# 08_MISC.net
KiCad netlist of a schematic drawn in Altium Designer
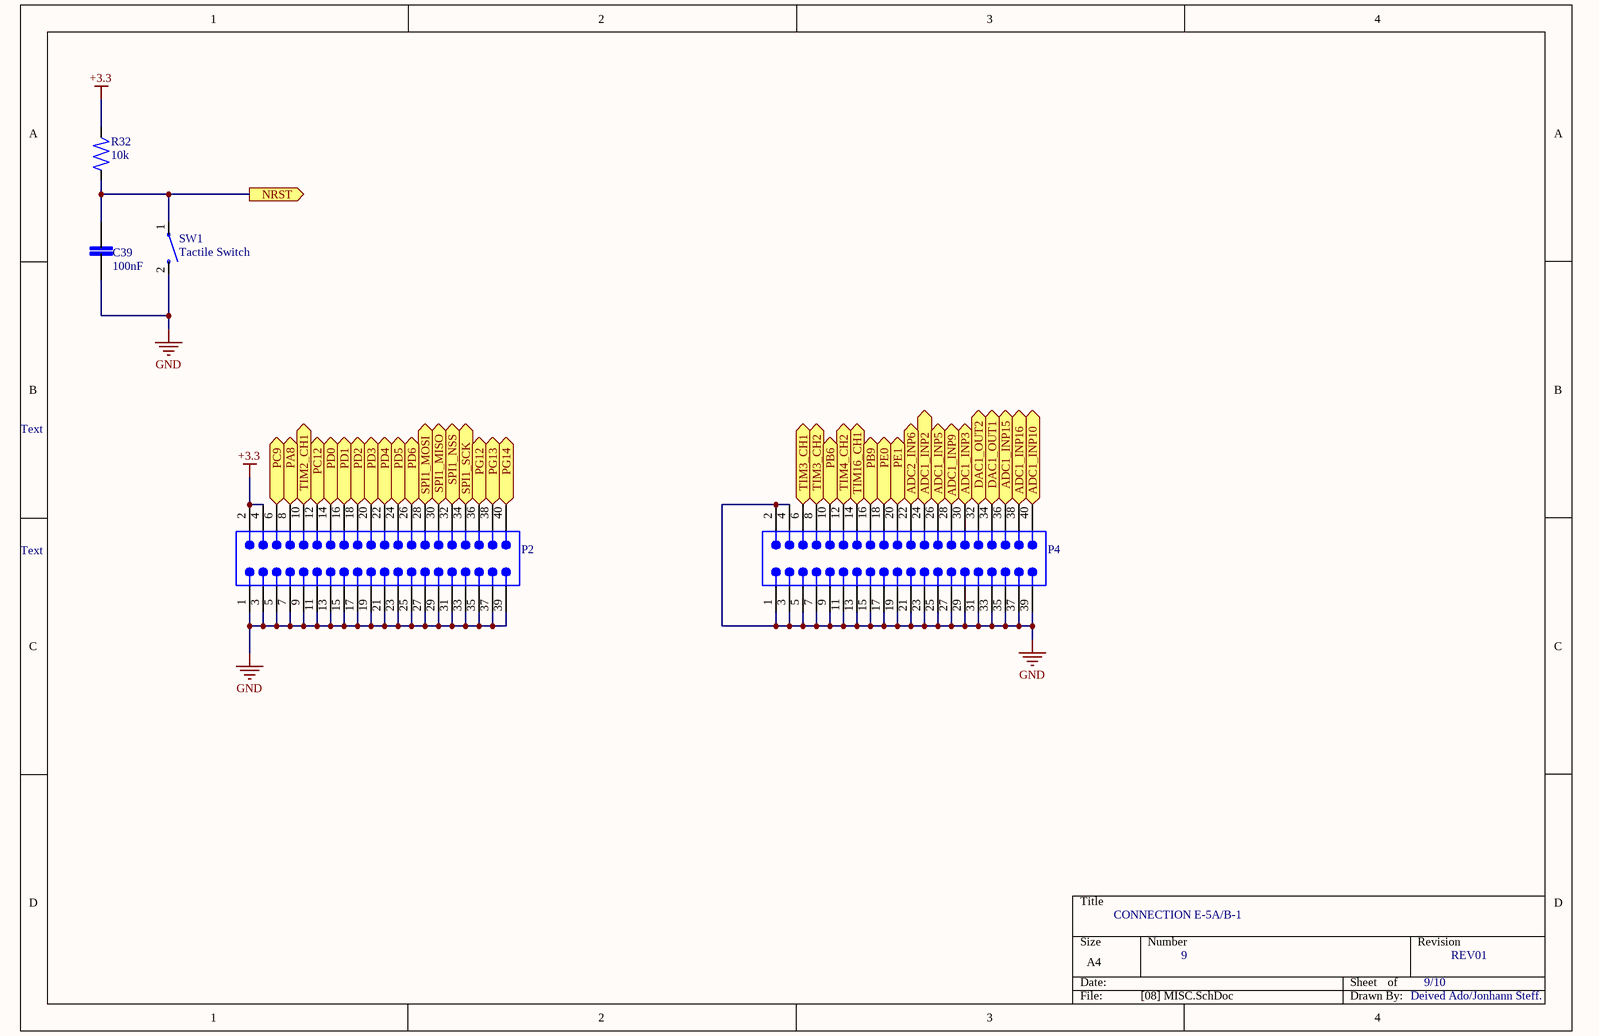
[diagram p0: [08] MISC.SchDoc]

(export (version "E")
  (design (tool "Eeschema 10.0.6"))
  (components
    (comp (ref "C39")
      (value "100nF")
      (footprint "CAP_0603")
      (description "Generic capacitor symbol")
      (libsource (lib "Integrated_Library_IST") (part "C_Small"))
    )
    (comp (ref "P2")
      (value "62504021621")
      (footprint "62504021621")
      (description "WR-BHD Male Box Header, THT Straight, pitch 2mm, 2 row, 40 pin")
      (fields (field (name "MANUFACTURER") "Wurth Elektronik"))
      (libsource (lib "WE - Electromechanical Components") (part "Header_Male_2R_40P"))
    )
    (comp (ref "P4")
      (value "62504021621")
      (footprint "62504021621")
      (description "WR-BHD Male Box Header, THT Straight, pitch 2mm, 2 row, 40 pin")
      (fields (field (name "MANUFACTURER") "Wurth Elektronik"))
      (libsource (lib "WE - Electromechanical Components") (part "Header_Male_2R_40P"))
    )
    (comp (ref "R32")
      (value "10k")
      (footprint "RES_0603")
      (description "Generic Resistor symbol")
      (libsource (lib "Integrated_Library_IST") (part "R_Small"))
    )
    (comp (ref "SW1")
      (value "Tactile Switch")
      (footprint "SW_1437566-3")
      (description "Switch Tactile OFF (ON) SPST Rectangular Button Gull Wing 0.05A 12VDC SMD Loose Piece")
      (fields
        (field (name "MANUFACTURER") "TE Connectivity / Alcoswitch")
        (field (name "MFR. PART #") "FSMSM")
      )
      (libsource (lib "Integrated_Library_IST") (part "Tactile Switch"))
    )
  )
  (nets
    (net (code "1") (name "+3.3") (class "Default")
      (node (ref "P2") (pin "2") (pinfunction "2_2") (pintype "passive"))
      (node (ref "P2") (pin "4") (pinfunction "4_4") (pintype "passive"))
      (node (ref "R32") (pin "2") (pinfunction "2_2") (pintype "passive"))
    )
    (net (code "2") (name "/ADC1_INP2") (class "Default")
      (node (ref "P4") (pin "24") (pinfunction "24_24") (pintype "passive"))
    )
    (net (code "3") (name "/ADC1_INP3") (class "Default")
      (node (ref "P4") (pin "30") (pinfunction "30_30") (pintype "passive"))
    )
    (net (code "4") (name "/ADC1_INP5") (class "Default")
      (node (ref "P4") (pin "26") (pinfunction "26_26") (pintype "passive"))
    )
    (net (code "5") (name "/ADC1_INP9") (class "Default")
      (node (ref "P4") (pin "28") (pinfunction "28_28") (pintype "passive"))
    )
    (net (code "6") (name "/ADC1_INP10") (class "Default")
      (node (ref "P4") (pin "40") (pinfunction "40_40") (pintype "passive"))
    )
    (net (code "7") (name "/ADC1_INP15") (class "Default")
      (node (ref "P4") (pin "36") (pinfunction "36_36") (pintype "passive"))
    )
    (net (code "8") (name "/ADC1_INP16") (class "Default")
      (node (ref "P4") (pin "38") (pinfunction "38_38") (pintype "passive"))
    )
    (net (code "9") (name "/ADC2_INP6") (class "Default")
      (node (ref "P4") (pin "22") (pinfunction "22_22") (pintype "passive"))
    )
    (net (code "10") (name "/DAC1_OUT1") (class "Default")
      (node (ref "P4") (pin "34") (pinfunction "34_34") (pintype "passive"))
    )
    (net (code "11") (name "/DAC1_OUT2") (class "Default")
      (node (ref "P4") (pin "32") (pinfunction "32_32") (pintype "passive"))
    )
    (net (code "12") (name "/NRST") (class "Default")
      (node (ref "C39") (pin "2") (pinfunction "2_2") (pintype "passive"))
      (node (ref "R32") (pin "1") (pinfunction "1_1") (pintype "passive"))
      (node (ref "SW1") (pin "1") (pinfunction "1_1") (pintype "passive"))
    )
    (net (code "13") (name "/PA8") (class "Default")
      (node (ref "P2") (pin "8") (pinfunction "8_8") (pintype "passive"))
    )
    (net (code "14") (name "/PB6") (class "Default")
      (node (ref "P4") (pin "10") (pinfunction "10_10") (pintype "passive"))
    )
    (net (code "15") (name "/PB9") (class "Default")
      (node (ref "P4") (pin "16") (pinfunction "16_16") (pintype "passive"))
    )
    (net (code "16") (name "/PC9") (class "Default")
      (node (ref "P2") (pin "6") (pinfunction "6_6") (pintype "passive"))
    )
    (net (code "17") (name "/PC12") (class "Default")
      (node (ref "P2") (pin "12") (pinfunction "12_12") (pintype "passive"))
    )
    (net (code "18") (name "/PD0") (class "Default")
      (node (ref "P2") (pin "14") (pinfunction "14_14") (pintype "passive"))
    )
    (net (code "19") (name "/PD1") (class "Default")
      (node (ref "P2") (pin "16") (pinfunction "16_16") (pintype "passive"))
    )
    (net (code "20") (name "/PD2") (class "Default")
      (node (ref "P2") (pin "18") (pinfunction "18_18") (pintype "passive"))
    )
    (net (code "21") (name "/PD3") (class "Default")
      (node (ref "P2") (pin "20") (pinfunction "20_20") (pintype "passive"))
    )
    (net (code "22") (name "/PD4") (class "Default")
      (node (ref "P2") (pin "22") (pinfunction "22_22") (pintype "passive"))
    )
    (net (code "23") (name "/PD5") (class "Default")
      (node (ref "P2") (pin "24") (pinfunction "24_24") (pintype "passive"))
    )
    (net (code "24") (name "/PD6") (class "Default")
      (node (ref "P2") (pin "26") (pinfunction "26_26") (pintype "passive"))
    )
    (net (code "25") (name "/PE0") (class "Default")
      (node (ref "P4") (pin "18") (pinfunction "18_18") (pintype "passive"))
    )
    (net (code "26") (name "/PE1") (class "Default")
      (node (ref "P4") (pin "20") (pinfunction "20_20") (pintype "passive"))
    )
    (net (code "27") (name "/PG12") (class "Default")
      (node (ref "P2") (pin "36") (pinfunction "36_36") (pintype "passive"))
    )
    (net (code "28") (name "/PG13") (class "Default")
      (node (ref "P2") (pin "38") (pinfunction "38_38") (pintype "passive"))
    )
    (net (code "29") (name "/PG14") (class "Default")
      (node (ref "P2") (pin "40") (pinfunction "40_40") (pintype "passive"))
    )
    (net (code "30") (name "/SPI1_MISO") (class "Default")
      (node (ref "P2") (pin "30") (pinfunction "30_30") (pintype "passive"))
    )
    (net (code "31") (name "/SPI1_MOSI") (class "Default")
      (node (ref "P2") (pin "28") (pinfunction "28_28") (pintype "passive"))
    )
    (net (code "32") (name "/SPI1_NSS") (class "Default")
      (node (ref "P2") (pin "32") (pinfunction "32_32") (pintype "passive"))
    )
    (net (code "33") (name "/SPI1_SCK") (class "Default")
      (node (ref "P2") (pin "34") (pinfunction "34_34") (pintype "passive"))
    )
    (net (code "34") (name "/TIM2_CH1") (class "Default")
      (node (ref "P2") (pin "10") (pinfunction "10_10") (pintype "passive"))
    )
    (net (code "35") (name "/TIM3_CH1") (class "Default")
      (node (ref "P4") (pin "6") (pinfunction "6_6") (pintype "passive"))
    )
    (net (code "36") (name "/TIM3_CH2") (class "Default")
      (node (ref "P4") (pin "8") (pinfunction "8_8") (pintype "passive"))
    )
    (net (code "37") (name "/TIM4_CH2") (class "Default")
      (node (ref "P4") (pin "12") (pinfunction "12_12") (pintype "passive"))
    )
    (net (code "38") (name "/TIM16_CH1") (class "Default")
      (node (ref "P4") (pin "14") (pinfunction "14_14") (pintype "passive"))
    )
    (net (code "39") (name "GND") (class "Default")
      (node (ref "C39") (pin "1") (pinfunction "1_1") (pintype "passive"))
      (node (ref "P2") (pin "1") (pinfunction "1_1") (pintype "passive"))
      (node (ref "P2") (pin "11") (pinfunction "11_11") (pintype "passive"))
      (node (ref "P2") (pin "13") (pinfunction "13_13") (pintype "passive"))
      (node (ref "P2") (pin "15") (pinfunction "15_15") (pintype "passive"))
      (node (ref "P2") (pin "17") (pinfunction "17_17") (pintype "passive"))
      (node (ref "P2") (pin "19") (pinfunction "19_19") (pintype "passive"))
      (node (ref "P2") (pin "21") (pinfunction "21_21") (pintype "passive"))
      (node (ref "P2") (pin "23") (pinfunction "23_23") (pintype "passive"))
      (node (ref "P2") (pin "25") (pinfunction "25_25") (pintype "passive"))
      (node (ref "P2") (pin "27") (pinfunction "27_27") (pintype "passive"))
      (node (ref "P2") (pin "29") (pinfunction "29_29") (pintype "passive"))
      (node (ref "P2") (pin "3") (pinfunction "3_3") (pintype "passive"))
      (node (ref "P2") (pin "31") (pinfunction "31_31") (pintype "passive"))
      (node (ref "P2") (pin "33") (pinfunction "33_33") (pintype "passive"))
      (node (ref "P2") (pin "35") (pinfunction "35_35") (pintype "passive"))
      (node (ref "P2") (pin "37") (pinfunction "37_37") (pintype "passive"))
      (node (ref "P2") (pin "39") (pinfunction "39_39") (pintype "passive"))
      (node (ref "P2") (pin "5") (pinfunction "5_5") (pintype "passive"))
      (node (ref "P2") (pin "7") (pinfunction "7_7") (pintype "passive"))
      (node (ref "P2") (pin "9") (pinfunction "9_9") (pintype "passive"))
      (node (ref "P4") (pin "1") (pinfunction "1_1") (pintype "passive"))
      (node (ref "P4") (pin "11") (pinfunction "11_11") (pintype "passive"))
      (node (ref "P4") (pin "13") (pinfunction "13_13") (pintype "passive"))
      (node (ref "P4") (pin "15") (pinfunction "15_15") (pintype "passive"))
      (node (ref "P4") (pin "17") (pinfunction "17_17") (pintype "passive"))
      (node (ref "P4") (pin "19") (pinfunction "19_19") (pintype "passive"))
      (node (ref "P4") (pin "2") (pinfunction "2_2") (pintype "passive"))
      (node (ref "P4") (pin "21") (pinfunction "21_21") (pintype "passive"))
      (node (ref "P4") (pin "23") (pinfunction "23_23") (pintype "passive"))
      (node (ref "P4") (pin "25") (pinfunction "25_25") (pintype "passive"))
      (node (ref "P4") (pin "27") (pinfunction "27_27") (pintype "passive"))
      (node (ref "P4") (pin "29") (pinfunction "29_29") (pintype "passive"))
      (node (ref "P4") (pin "3") (pinfunction "3_3") (pintype "passive"))
      (node (ref "P4") (pin "31") (pinfunction "31_31") (pintype "passive"))
      (node (ref "P4") (pin "33") (pinfunction "33_33") (pintype "passive"))
      (node (ref "P4") (pin "35") (pinfunction "35_35") (pintype "passive"))
      (node (ref "P4") (pin "37") (pinfunction "37_37") (pintype "passive"))
      (node (ref "P4") (pin "39") (pinfunction "39_39") (pintype "passive"))
      (node (ref "P4") (pin "4") (pinfunction "4_4") (pintype "passive"))
      (node (ref "P4") (pin "5") (pinfunction "5_5") (pintype "passive"))
      (node (ref "P4") (pin "7") (pinfunction "7_7") (pintype "passive"))
      (node (ref "P4") (pin "9") (pinfunction "9_9") (pintype "passive"))
      (node (ref "SW1") (pin "2") (pinfunction "2_2") (pintype "passive"))
    )
  )
)
